# DS141-1_0.net
KiCad netlist of a schematic drawn in Altium Designer
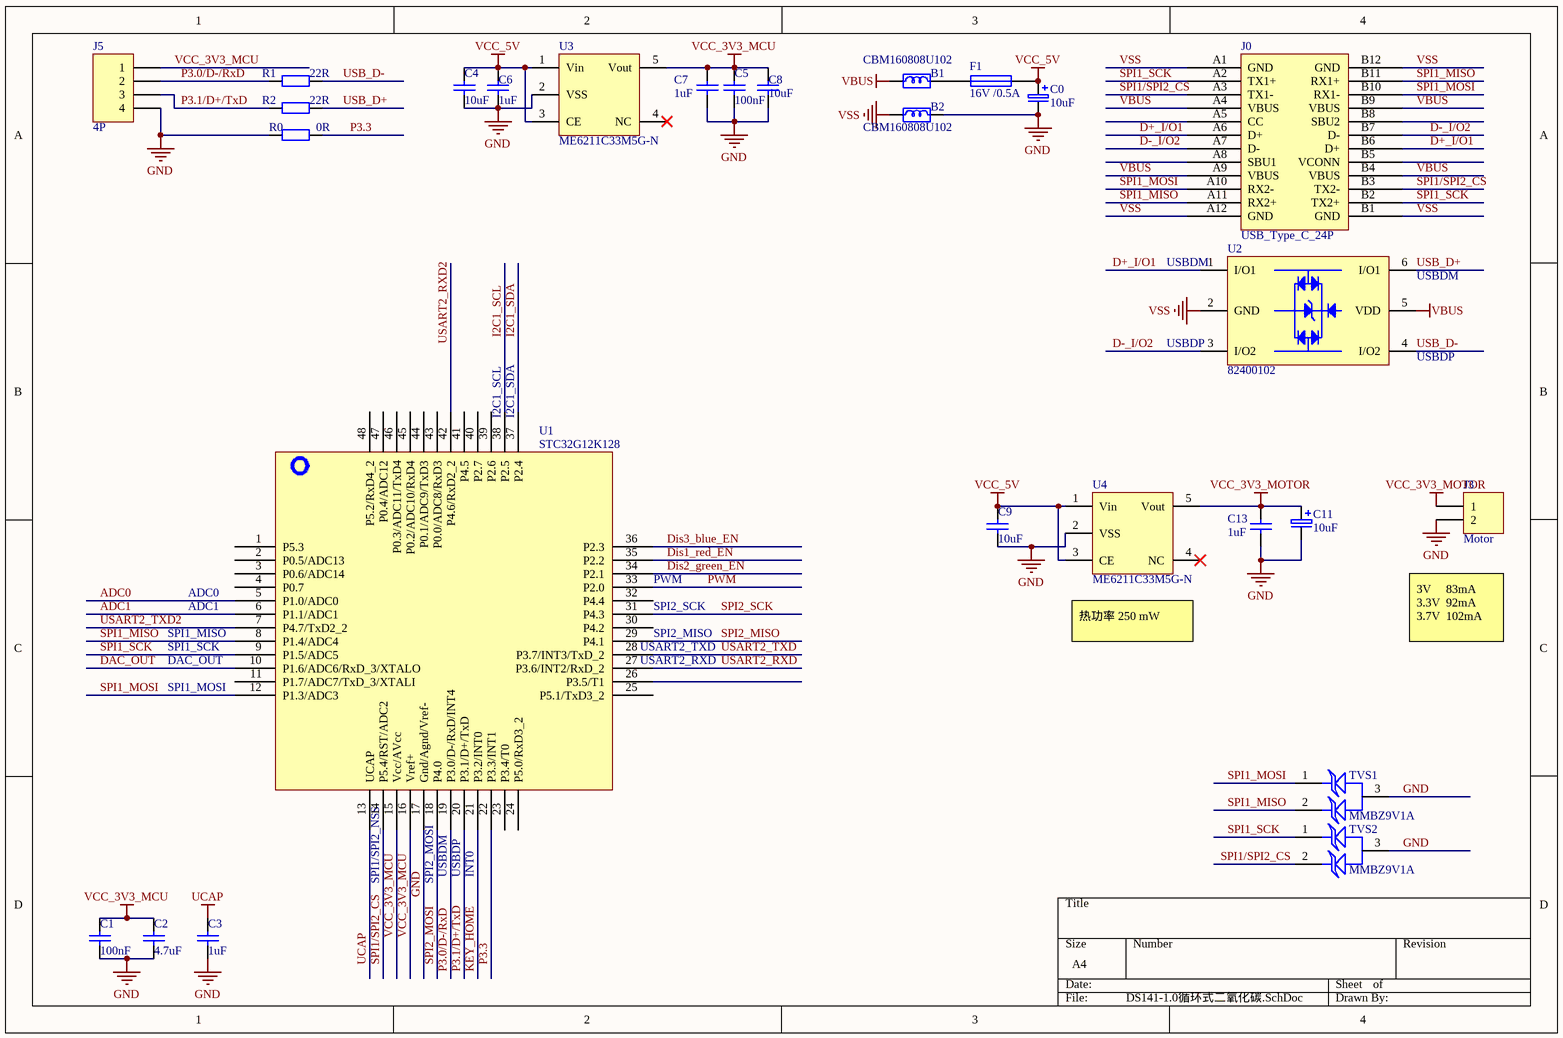
[diagram p0: DS141-1.0循环式二氧化碳.SchDoc]

(export (version "E")
  (design (tool "Eeschema 10.0.6"))
  (components
    (comp (ref "B1")
      (value "CBM160808U102")
      (footprint "0603Bead")
      (description "贴片磁珠")
      (libsource (lib "AD_SCH") (part "Chip Ferrite Bead 0606"))
    )
    (comp (ref "B2")
      (value "CBM160808U102")
      (footprint "0603Bead")
      (description "贴片磁珠")
      (libsource (lib "AD_SCH") (part "Chip Ferrite Bead 0606"))
    )
    (comp (ref "C0")
      (value "10uF")
      (footprint "AVX_3216-18(1206)_SMD")
      (description "钽电容")
      (fields (field (name "Comment") "AVX_10uF/16V ±10％(C106)"))
      (libsource (lib "AD_SCH") (part "AVX_10uF/16V ±10％(C106)"))
    )
    (comp (ref "C1")
      (value "100nF")
      (footprint "0603CAP")
      (description "贴片电容")
      (fields (field (name "Comment") "SMDCAP00013"))
      (libsource (lib "AD_SCH") (part "MLCC 100nF 50V ±10％ 0603"))
    )
    (comp (ref "C2")
      (value "4.7uF")
      (footprint "0603CAP")
      (description "贴片电容")
      (fields (field (name "Comment") "SMDCAP00012"))
      (libsource (lib "AD_SCH") (part "MLCC 4.7uF 50V ±10％ 0603"))
    )
    (comp (ref "C3")
      (value "1uF")
      (footprint "0603CAP")
      (description "贴片电容")
      (fields (field (name "Comment") "SMDCAP00015"))
      (libsource (lib "AD_SCH") (part "MLCC 1uF 50V ±10％ 0603"))
    )
    (comp (ref "C4")
      (value "10uF")
      (footprint "1206CAP")
      (description "贴片电容")
      (fields (field (name "Comment") "MLCC 10uF 50V ±20％ 1206"))
      (libsource (lib "AD_SCH") (part "MLCC 10uF 50V ±20％ 1206"))
    )
    (comp (ref "C5")
      (value "100nF")
      (footprint "0603CAP")
      (description "贴片电容")
      (fields (field (name "Comment") "SMDCAP00013"))
      (libsource (lib "AD_SCH") (part "MLCC 100nF 50V ±10％ 0603"))
    )
    (comp (ref "C6")
      (value "1uF")
      (footprint "0603CAP")
      (description "贴片电容")
      (fields (field (name "Comment") "SMDCAP00015"))
      (libsource (lib "AD_SCH") (part "MLCC 1uF 50V ±10％ 0603"))
    )
    (comp (ref "C7")
      (value "1uF")
      (footprint "0603CAP")
      (description "贴片电容")
      (fields (field (name "Comment") "SMDCAP00015"))
      (libsource (lib "AD_SCH") (part "MLCC 1uF 50V ±10％ 0603"))
    )
    (comp (ref "C8")
      (value "10uF")
      (footprint "1206CAP")
      (description "贴片电容")
      (fields (field (name "Comment") "MLCC 10uF 50V ±20％ 1206"))
      (libsource (lib "AD_SCH") (part "MLCC 10uF 50V ±20％ 1206"))
    )
    (comp (ref "C9")
      (value "10uF")
      (footprint "1206CAP")
      (description "贴片电容")
      (fields (field (name "Comment") "MLCC 10uF 50V ±20％ 1206"))
      (libsource (lib "AD_SCH") (part "MLCC 10uF 50V ±20％ 1206"))
    )
    (comp (ref "C11")
      (value "10uF")
      (footprint "AVX_3216-18(1206)_SMD")
      (description "钽电容")
      (fields (field (name "Comment") "AVX_10uF/16V ±10％(C106)"))
      (libsource (lib "AD_SCH") (part "AVX_10uF/16V ±10％(C106)"))
    )
    (comp (ref "C13")
      (value "1uF")
      (footprint "0603CAP")
      (description "贴片电容")
      (fields (field (name "Comment") "SMDCAP00015"))
      (libsource (lib "AD_SCH") (part "MLCC 1uF 50V ±10％ 0603"))
    )
    (comp (ref "F1")
      (value "16V /0.5A")
      (footprint "1206FUSE")
      (description "贴片自恢复保险丝 16V /0.5A")
      (fields (field (name "Comment") "SMD1206-050C-16V"))
      (libsource (lib "AD_SCH") (part "SMD1206-050C-16V"))
    )
    (comp (ref "J0")
      (value "USB_Type_C_24P")
      (footprint "USB_TYPE_C_24P_Receptacle")
      (libsource (lib "AD_SCH") (part "USB_Type_C_24P"))
    )
    (comp (ref "J3")
      (value "Motor")
      (footprint "SIP2")
      (description "单排直针")
      (fields (field (name "Comment") "SL000000042"))
      (libsource (lib "AD_SCH") (part "DIP2 单排直针 1*40P 间距2.54mm 针长11mm 铜"))
    )
    (comp (ref "J5")
      (value "4P")
      (footprint "H4")
      (description "单排直针")
      (fields (field (name "Comment") "DIP4单排直针  间距2mm 针长11mm 铜"))
      (libsource (lib "AD_SCH") (part "DIP4单排直针  间距2mm 针长11mm 铜"))
    )
    (comp (ref "R0")
      (value "0R")
      (footprint "0603RES")
      (description "贴片电阻")
      (fields (field (name "Comment") "Chip 0R 1/16W ±1％ 0603"))
      (libsource (lib "AD_SCH") (part "Chip 0R 1/16W ±1％ 0603"))
    )
    (comp (ref "R1")
      (value "22R")
      (footprint "0603RES")
      (description "贴片电阻")
      (fields (field (name "Comment") "Chip 22R 1/16W ±1％ 0603"))
      (libsource (lib "AD_SCH") (part "Chip 22R 1/16W ±1％ 0603"))
    )
    (comp (ref "R2")
      (value "22R")
      (footprint "0603RES")
      (description "贴片电阻")
      (fields (field (name "Comment") "Chip 22R 1/16W ±1％ 0603"))
      (libsource (lib "AD_SCH") (part "Chip 22R 1/16W ±1％ 0603"))
    )
    (comp (ref "TVS1")
      (value "MMBZ9V1A")
      (footprint "SOT23")
      (description "瞬态抑制二极管")
      (libsource (lib "AD_SCH") (part "TVS"))
    )
    (comp (ref "TVS2")
      (value "MMBZ9V1A")
      (footprint "SOT23")
      (description "瞬态抑制二极管")
      (libsource (lib "AD_SCH") (part "TVS"))
    )
    (comp (ref "U1")
      (value "STC32G12K128")
      (footprint "LQFP-48")
      (description "单片机芯片")
      (fields (field (name "Comment") "STC32G12K128_35I LQFP48"))
      (libsource (lib "AD_SCH") (part "STC32G12K128_35I LQFP48"))
    )
    (comp (ref "U2")
      (value "82400102")
      (footprint "SOT23-6")
      (description "瞬态抑制二极管(TVS)")
      (libsource (lib "AD_SCH") (part "82400102"))
    )
    (comp (ref "U3")
      (value "ME6211C33M5G-N")
      (footprint "SOT23-5")
      (description "稳压芯片")
      (libsource (lib "AD_SCH") (part "ME6211C33M5G-N"))
    )
    (comp (ref "U4")
      (value "ME6211C33M5G-N")
      (footprint "SOT23-5")
      (description "稳压芯片")
      (libsource (lib "AD_SCH") (part "ME6211C33M5G-N"))
    )
  )
  (nets
    (net (code "1") (name "/ADC0") (class "Default")
      (node (ref "U1") (pin "5") (pinfunction "P1.0/ADC0_5") (pintype "passive"))
    )
    (net (code "2") (name "/ADC1") (class "Default")
      (node (ref "U1") (pin "6") (pinfunction "P1.1/ADC1_6") (pintype "passive"))
    )
    (net (code "3") (name "/D+_I{slash}O1") (class "Default")
      (node (ref "J0") (pin "A6") (pinfunction "D+_A6") (pintype "passive"))
      (node (ref "J0") (pin "B6") (pinfunction "D+_B6") (pintype "passive"))
      (node (ref "U2") (pin "1") (pinfunction "I/O1_1") (pintype "passive"))
    )
    (net (code "4") (name "/D-_I{slash}O2") (class "Default")
      (node (ref "J0") (pin "A7") (pinfunction "D-_A7") (pintype "passive"))
      (node (ref "J0") (pin "B7") (pinfunction "D-_B7") (pintype "passive"))
      (node (ref "U2") (pin "3") (pinfunction "I/O2_3") (pintype "passive"))
    )
    (net (code "5") (name "/DAC_OUT") (class "Default")
      (node (ref "U1") (pin "10") (pinfunction "P1.6/ADC6/RxD_3/XTALO_10") (pintype "passive"))
    )
    (net (code "6") (name "/Dis1_red_EN") (class "Default")
      (node (ref "U1") (pin "35") (pinfunction "P2.2_35") (pintype "passive"))
    )
    (net (code "7") (name "/Dis2_green_EN") (class "Default")
      (node (ref "U1") (pin "34") (pinfunction "P2.1_34") (pintype "passive"))
    )
    (net (code "8") (name "/Dis3_blue_EN") (class "Default")
      (node (ref "U1") (pin "36") (pinfunction "P2.3_36") (pintype "passive"))
    )
    (net (code "9") (name "/I2C1_SCL") (class "Default")
      (node (ref "U1") (pin "38") (pinfunction "P2.5_38") (pintype "passive"))
    )
    (net (code "10") (name "/I2C1_SDA") (class "Default")
      (node (ref "U1") (pin "37") (pinfunction "P2.4_37") (pintype "passive"))
    )
    (net (code "11") (name "/KEY_HOME") (class "Default")
      (node (ref "U1") (pin "21") (pinfunction "P3.2/INT0_21") (pintype "passive"))
    )
    (net (code "12") (name "/P3.0{slash}D-{slash}RxD") (class "Default")
      (node (ref "J5") (pin "2") (pinfunction "2_2") (pintype "passive"))
      (node (ref "R1") (pin "1") (pinfunction "1_1") (pintype "passive"))
      (node (ref "U1") (pin "19") (pinfunction "P3.0/D-/RxD/INT4_19") (pintype "passive"))
    )
    (net (code "13") (name "/P3.1{slash}D+{slash}TxD") (class "Default")
      (node (ref "J5") (pin "3") (pinfunction "3_3") (pintype "passive"))
      (node (ref "R2") (pin "1") (pinfunction "1_1") (pintype "passive"))
      (node (ref "U1") (pin "20") (pinfunction "P3.1/D+/TxD_20") (pintype "passive"))
    )
    (net (code "14") (name "/P3.3") (class "Default")
      (node (ref "R0") (pin "2") (pinfunction "2_2") (pintype "passive"))
      (node (ref "U1") (pin "22") (pinfunction "P3.3/INT1_22") (pintype "passive"))
    )
    (net (code "15") (name "/PWM") (class "Default")
      (node (ref "U1") (pin "33") (pinfunction "P2.0_33") (pintype "passive"))
    )
    (net (code "16") (name "/SPI1_MISO") (class "Default")
      (node (ref "J0") (pin "A11") (pinfunction "RX2+_A11") (pintype "passive"))
      (node (ref "J0") (pin "B11") (pinfunction "RX1+_B11") (pintype "passive"))
      (node (ref "TVS1") (pin "2") (pinfunction "2_2") (pintype "passive"))
      (node (ref "U1") (pin "8") (pinfunction "P1.4/ADC4_8") (pintype "passive"))
    )
    (net (code "17") (name "/SPI1_MOSI") (class "Default")
      (node (ref "J0") (pin "A10") (pinfunction "RX2-_A10") (pintype "passive"))
      (node (ref "J0") (pin "B10") (pinfunction "RX1-_B10") (pintype "passive"))
      (node (ref "TVS1") (pin "1") (pinfunction "1_1") (pintype "passive"))
      (node (ref "U1") (pin "12") (pinfunction "P1.3/ADC3_12") (pintype "passive"))
    )
    (net (code "18") (name "/SPI1_SCK") (class "Default")
      (node (ref "J0") (pin "A2") (pinfunction "TX1+_A2") (pintype "passive"))
      (node (ref "J0") (pin "B2") (pinfunction "TX2+_B2") (pintype "passive"))
      (node (ref "TVS2") (pin "1") (pinfunction "1_1") (pintype "passive"))
      (node (ref "U1") (pin "9") (pinfunction "P1.5/ADC5_9") (pintype "passive"))
    )
    (net (code "19") (name "/SPI1{slash}SPI2_CS") (class "Default")
      (node (ref "J0") (pin "A3") (pinfunction "TX1-_A3") (pintype "passive"))
      (node (ref "J0") (pin "B3") (pinfunction "TX2-_B3") (pintype "passive"))
      (node (ref "TVS2") (pin "2") (pinfunction "2_2") (pintype "passive"))
      (node (ref "U1") (pin "14") (pinfunction "P5.4/RST/ADC2_14") (pintype "passive"))
    )
    (net (code "20") (name "/SPI2_MISO") (class "Default")
      (node (ref "U1") (pin "29") (pinfunction "P4.1_29") (pintype "passive"))
    )
    (net (code "21") (name "/SPI2_MOSI") (class "Default")
      (node (ref "U1") (pin "18") (pinfunction "P4.0_18") (pintype "passive"))
    )
    (net (code "22") (name "/SPI2_SCK") (class "Default")
      (node (ref "U1") (pin "31") (pinfunction "P4.3_31") (pintype "passive"))
    )
    (net (code "23") (name "/USART2_RXD") (class "Default")
      (node (ref "U1") (pin "27") (pinfunction "P3.6/INT2/RxD_2_27") (pintype "passive"))
    )
    (net (code "24") (name "/USART2_RXD2") (class "Default")
      (node (ref "U1") (pin "42") (pinfunction "P4.6/RxD2_2_42") (pintype "passive"))
    )
    (net (code "25") (name "/USART2_TXD") (class "Default")
      (node (ref "U1") (pin "28") (pinfunction "P3.7/INT3/TxD_2_28") (pintype "passive"))
    )
    (net (code "26") (name "/USART2_TXD2") (class "Default")
      (node (ref "U1") (pin "7") (pinfunction "P4.7/TxD2_2_7") (pintype "passive"))
    )
    (net (code "27") (name "/USB_D+") (class "Default")
      (node (ref "R2") (pin "2") (pinfunction "2_2") (pintype "passive"))
      (node (ref "U2") (pin "6") (pinfunction "I/O1_6") (pintype "passive"))
    )
    (net (code "28") (name "/USB_D-") (class "Default")
      (node (ref "R1") (pin "2") (pinfunction "2_2") (pintype "passive"))
      (node (ref "U2") (pin "4") (pinfunction "I/O2_4") (pintype "passive"))
    )
    (net (code "29") (name "GND") (class "Default")
      (node (ref "B2") (pin "2") (pinfunction "2_2") (pintype "passive"))
      (node (ref "C0") (pin "2") (pinfunction "2_2") (pintype "passive"))
      (node (ref "C1") (pin "1") (pinfunction "1_1") (pintype "passive"))
      (node (ref "C11") (pin "2") (pinfunction "2_2") (pintype "passive"))
      (node (ref "C13") (pin "1") (pinfunction "1_1") (pintype "passive"))
      (node (ref "C2") (pin "1") (pinfunction "1_1") (pintype "passive"))
      (node (ref "C3") (pin "1") (pinfunction "1_1") (pintype "passive"))
      (node (ref "C4") (pin "1") (pinfunction "1_1") (pintype "passive"))
      (node (ref "C5") (pin "1") (pinfunction "1_1") (pintype "passive"))
      (node (ref "C6") (pin "1") (pinfunction "1_1") (pintype "passive"))
      (node (ref "C7") (pin "1") (pinfunction "1_1") (pintype "passive"))
      (node (ref "C8") (pin "1") (pinfunction "1_1") (pintype "passive"))
      (node (ref "C9") (pin "1") (pinfunction "1_1") (pintype "passive"))
      (node (ref "J3") (pin "2") (pinfunction "2_2") (pintype "passive"))
      (node (ref "J5") (pin "4") (pinfunction "4_4") (pintype "passive"))
      (node (ref "R0") (pin "1") (pinfunction "1_1") (pintype "passive"))
      (node (ref "TVS1") (pin "3") (pinfunction "3_3") (pintype "passive"))
      (node (ref "TVS2") (pin "3") (pinfunction "3_3") (pintype "passive"))
      (node (ref "U1") (pin "17") (pinfunction "Gnd/Agnd/Vref-_17") (pintype "passive"))
      (node (ref "U3") (pin "2") (pinfunction "VSS_2") (pintype "passive"))
      (node (ref "U4") (pin "2") (pinfunction "VSS_2") (pintype "passive"))
    )
    (net (code "30") (name "Net-(B1-Pad2)") (class "Default")
      (node (ref "B1") (pin "2") (pinfunction "2_2") (pintype "passive"))
      (node (ref "F1") (pin "1") (pinfunction "1_1") (pintype "passive"))
    )
    (net (code "31") (name "UCAP") (class "Default")
      (node (ref "C3") (pin "2") (pinfunction "2_2") (pintype "passive"))
      (node (ref "U1") (pin "13") (pinfunction "UCAP_13") (pintype "passive"))
    )
    (net (code "32") (name "VBUS") (class "Default")
      (node (ref "B1") (pin "1") (pinfunction "1_1") (pintype "passive"))
      (node (ref "J0") (pin "A4") (pinfunction "VBUS_A4") (pintype "passive"))
      (node (ref "J0") (pin "A9") (pinfunction "VBUS_A9") (pintype "passive"))
      (node (ref "J0") (pin "B4") (pinfunction "VBUS_B4") (pintype "passive"))
      (node (ref "J0") (pin "B9") (pinfunction "VBUS_B9") (pintype "passive"))
      (node (ref "U2") (pin "5") (pinfunction "VDD_5") (pintype "passive"))
    )
    (net (code "33") (name "VCC_3V3_MCU") (class "Default")
      (node (ref "C1") (pin "2") (pinfunction "2_2") (pintype "passive"))
      (node (ref "C2") (pin "2") (pinfunction "2_2") (pintype "passive"))
      (node (ref "C5") (pin "2") (pinfunction "2_2") (pintype "passive"))
      (node (ref "C7") (pin "2") (pinfunction "2_2") (pintype "passive"))
      (node (ref "C8") (pin "2") (pinfunction "2_2") (pintype "passive"))
      (node (ref "J5") (pin "1") (pinfunction "1_1") (pintype "passive"))
      (node (ref "U1") (pin "15") (pinfunction "Vcc/AVcc_15") (pintype "passive"))
      (node (ref "U1") (pin "16") (pinfunction "Vref+_16") (pintype "passive"))
      (node (ref "U3") (pin "5") (pinfunction "Vout_5") (pintype "passive"))
    )
    (net (code "34") (name "VCC_3V3_MOTOR") (class "Default")
      (node (ref "C11") (pin "1") (pinfunction "1_1") (pintype "passive"))
      (node (ref "C13") (pin "2") (pinfunction "2_2") (pintype "passive"))
      (node (ref "J3") (pin "1") (pinfunction "1_1") (pintype "passive"))
      (node (ref "U4") (pin "5") (pinfunction "Vout_5") (pintype "passive"))
    )
    (net (code "35") (name "VCC_5V") (class "Default")
      (node (ref "C0") (pin "1") (pinfunction "1_1") (pintype "passive"))
      (node (ref "C4") (pin "2") (pinfunction "2_2") (pintype "passive"))
      (node (ref "C6") (pin "2") (pinfunction "2_2") (pintype "passive"))
      (node (ref "C9") (pin "2") (pinfunction "2_2") (pintype "passive"))
      (node (ref "F1") (pin "2") (pinfunction "2_2") (pintype "passive"))
      (node (ref "U3") (pin "1") (pinfunction "Vin_1") (pintype "passive"))
      (node (ref "U3") (pin "3") (pinfunction "CE_3") (pintype "passive"))
      (node (ref "U4") (pin "1") (pinfunction "Vin_1") (pintype "passive"))
      (node (ref "U4") (pin "3") (pinfunction "CE_3") (pintype "passive"))
    )
    (net (code "36") (name "VSS") (class "Default")
      (node (ref "B2") (pin "1") (pinfunction "1_1") (pintype "passive"))
      (node (ref "J0") (pin "A1") (pinfunction "GND_A1") (pintype "passive"))
      (node (ref "J0") (pin "A12") (pinfunction "GND_A12") (pintype "passive"))
      (node (ref "J0") (pin "B1") (pinfunction "GND_B1") (pintype "passive"))
      (node (ref "J0") (pin "B12") (pinfunction "GND_B12") (pintype "passive"))
      (node (ref "U2") (pin "2") (pinfunction "GND_2") (pintype "passive"))
    )
    (net (code "37") (name "unconnected-(J0-CC-PadA5)") (class "Default")
      (node (ref "J0") (pin "A5") (pinfunction "CC_A5") (pintype "passive"))
    )
    (net (code "38") (name "unconnected-(J0-SBU1-PadA8)") (class "Default")
      (node (ref "J0") (pin "A8") (pinfunction "SBU1_A8") (pintype "passive"))
    )
    (net (code "39") (name "unconnected-(J0-SBU2-PadB8)") (class "Default")
      (node (ref "J0") (pin "B8") (pinfunction "SBU2_B8") (pintype "passive"))
    )
    (net (code "40") (name "unconnected-(J0-VCONN-PadB5)") (class "Default")
      (node (ref "J0") (pin "B5") (pinfunction "VCONN_B5") (pintype "passive"))
    )
    (net (code "41") (name "unconnected-(U1-P0.0{slash}ADC8{slash}RxD3-Pad43)") (class "Default")
      (node (ref "U1") (pin "43") (pinfunction "P0.0/ADC8/RxD3_43") (pintype "passive"))
    )
    (net (code "42") (name "unconnected-(U1-P0.1{slash}ADC9{slash}TxD3-Pad44)") (class "Default")
      (node (ref "U1") (pin "44") (pinfunction "P0.1/ADC9/TxD3_44") (pintype "passive"))
    )
    (net (code "43") (name "unconnected-(U1-P0.2{slash}ADC10{slash}RxD4-Pad45)") (class "Default")
      (node (ref "U1") (pin "45") (pinfunction "P0.2/ADC10/RxD4_45") (pintype "passive"))
    )
    (net (code "44") (name "unconnected-(U1-P0.3{slash}ADC11{slash}TxD4-Pad46)") (class "Default")
      (node (ref "U1") (pin "46") (pinfunction "P0.3/ADC11/TxD4_46") (pintype "passive"))
    )
    (net (code "45") (name "unconnected-(U1-P0.4{slash}ADC12-Pad47)") (class "Default")
      (node (ref "U1") (pin "47") (pinfunction "P0.4/ADC12_47") (pintype "passive"))
    )
    (net (code "46") (name "unconnected-(U1-P0.5{slash}ADC13-Pad2)") (class "Default")
      (node (ref "U1") (pin "2") (pinfunction "P0.5/ADC13_2") (pintype "passive"))
    )
    (net (code "47") (name "unconnected-(U1-P0.6{slash}ADC14-Pad3)") (class "Default")
      (node (ref "U1") (pin "3") (pinfunction "P0.6/ADC14_3") (pintype "passive"))
    )
    (net (code "48") (name "unconnected-(U1-P0.7-Pad4)") (class "Default")
      (node (ref "U1") (pin "4") (pinfunction "P0.7_4") (pintype "passive"))
    )
    (net (code "49") (name "unconnected-(U1-P1.7{slash}ADC7{slash}TxD_3{slash}XTALI-Pad11)") (class "Default")
      (node (ref "U1") (pin "11") (pinfunction "P1.7/ADC7/TxD_3/XTALI_11") (pintype "passive"))
    )
    (net (code "50") (name "unconnected-(U1-P2.6-Pad39)") (class "Default")
      (node (ref "U1") (pin "39") (pinfunction "P2.6_39") (pintype "passive"))
    )
    (net (code "51") (name "unconnected-(U1-P2.7-Pad40)") (class "Default")
      (node (ref "U1") (pin "40") (pinfunction "P2.7_40") (pintype "passive"))
    )
    (net (code "52") (name "unconnected-(U1-P3.4{slash}T0-Pad23)") (class "Default")
      (node (ref "U1") (pin "23") (pinfunction "P3.4/T0_23") (pintype "passive"))
    )
    (net (code "53") (name "unconnected-(U1-P3.5{slash}T1-Pad26)") (class "Default")
      (node (ref "U1") (pin "26") (pinfunction "P3.5/T1_26") (pintype "passive"))
    )
    (net (code "54") (name "unconnected-(U1-P4.2-Pad30)") (class "Default")
      (node (ref "U1") (pin "30") (pinfunction "P4.2_30") (pintype "passive"))
    )
    (net (code "55") (name "unconnected-(U1-P4.4-Pad32)") (class "Default")
      (node (ref "U1") (pin "32") (pinfunction "P4.4_32") (pintype "passive"))
    )
    (net (code "56") (name "unconnected-(U1-P4.5-Pad41)") (class "Default")
      (node (ref "U1") (pin "41") (pinfunction "P4.5_41") (pintype "passive"))
    )
    (net (code "57") (name "unconnected-(U1-P5.0{slash}RxD3_2-Pad24)") (class "Default")
      (node (ref "U1") (pin "24") (pinfunction "P5.0/RxD3_2_24") (pintype "passive"))
    )
    (net (code "58") (name "unconnected-(U1-P5.1{slash}TxD3_2-Pad25)") (class "Default")
      (node (ref "U1") (pin "25") (pinfunction "P5.1/TxD3_2_25") (pintype "passive"))
    )
    (net (code "59") (name "unconnected-(U1-P5.2{slash}RxD4_2-Pad48)") (class "Default")
      (node (ref "U1") (pin "48") (pinfunction "P5.2/RxD4_2_48") (pintype "passive"))
    )
    (net (code "60") (name "unconnected-(U1-P5.3-Pad1)") (class "Default")
      (node (ref "U1") (pin "1") (pinfunction "P5.3_1") (pintype "passive"))
    )
    (net (code "61") (name "unconnected-(U3-NC-Pad4)") (class "Default")
      (node (ref "U3") (pin "4") (pinfunction "NC_4") (pintype "passive+no_connect"))
    )
    (net (code "62") (name "unconnected-(U4-NC-Pad4)") (class "Default")
      (node (ref "U4") (pin "4") (pinfunction "NC_4") (pintype "passive+no_connect"))
    )
  )
)
